# Temp.net
KiCad netlist of a schematic drawn in EAGLE
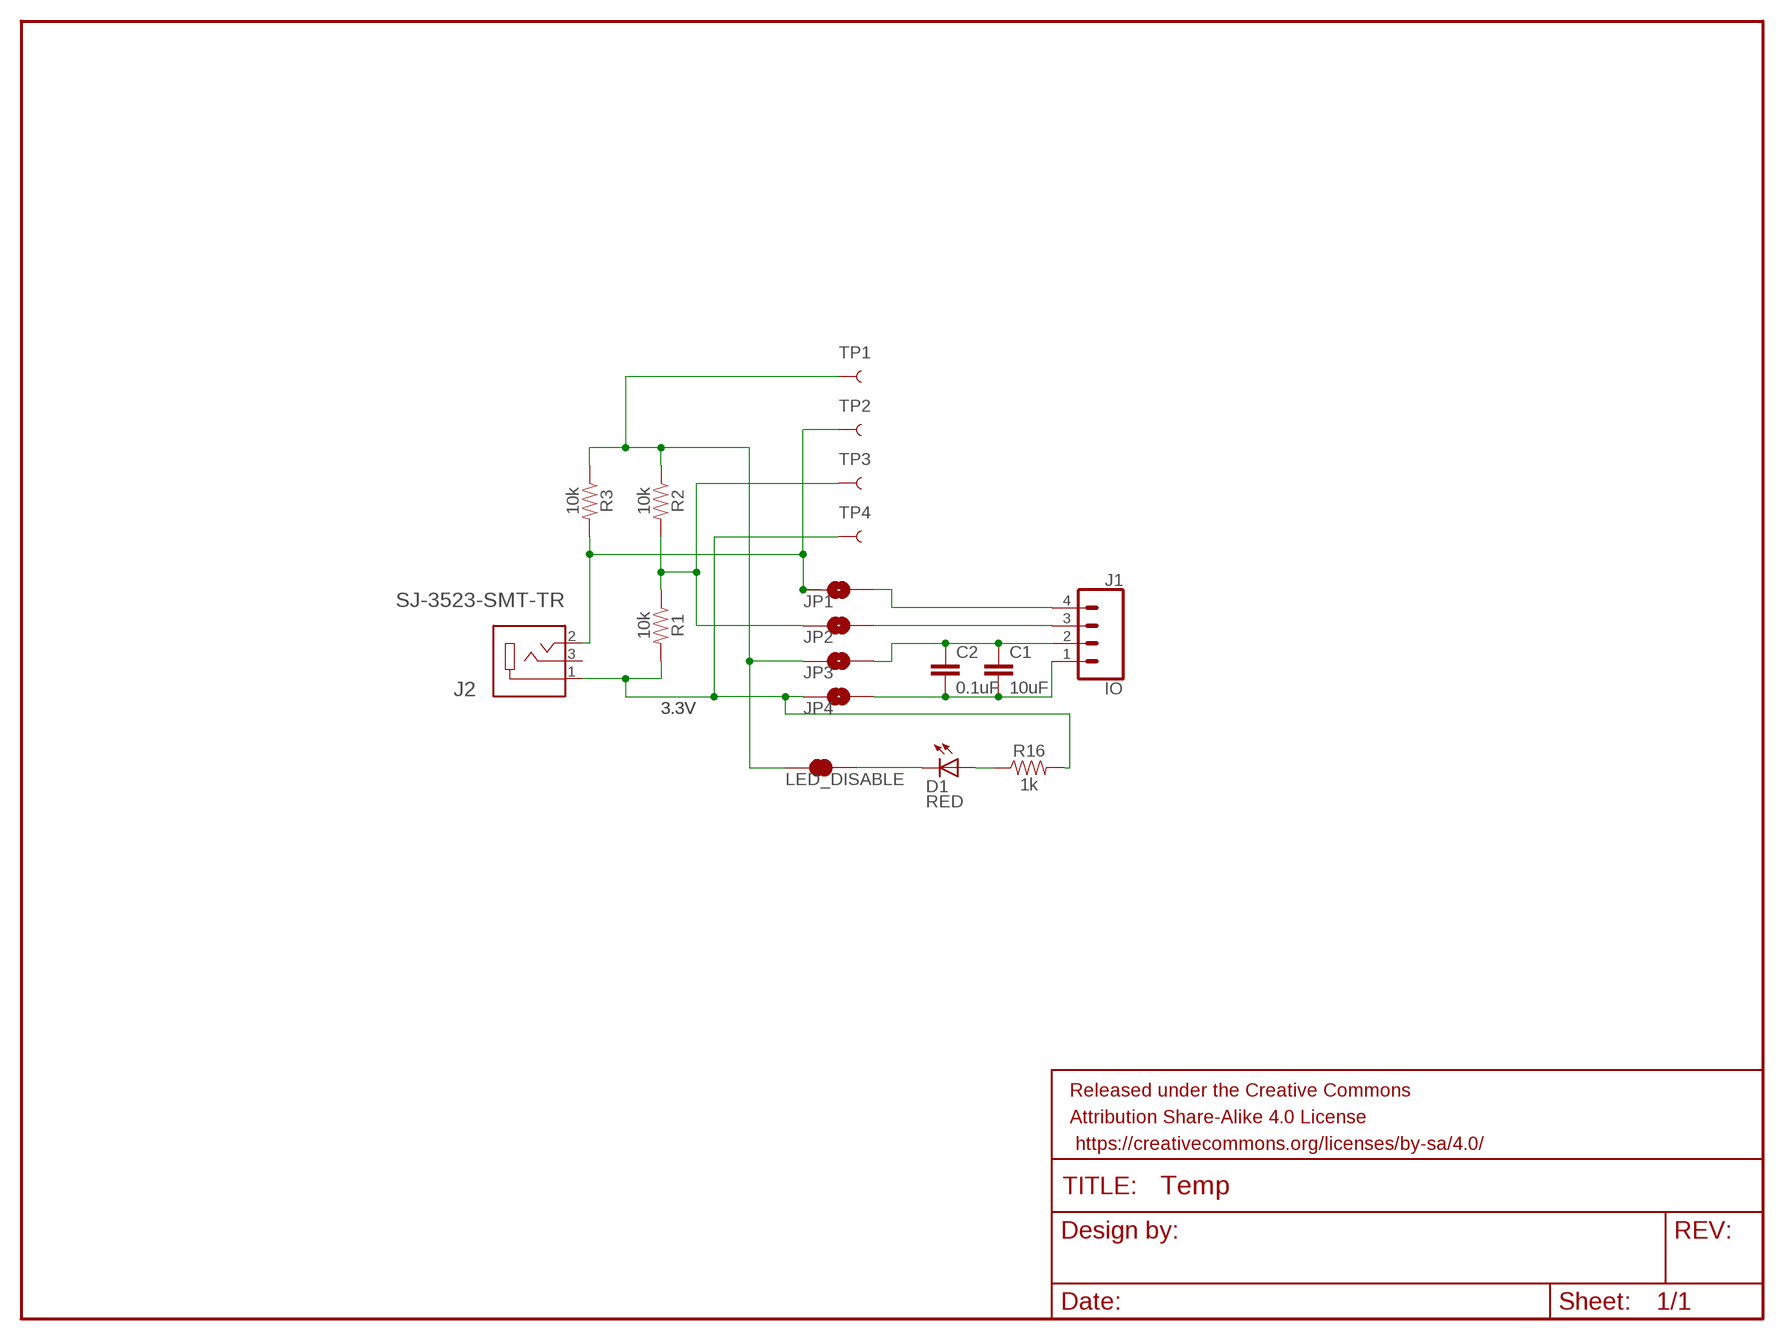
[diagram p0: schematic, sheet 1]

(export (version "E")
  (design (tool "Eeschema 10.0.6"))
  (components
    (comp (ref "C1")
      (value "10uF")
      (footprint "eagle-import:0603")
      (libsource (lib "eagle-import") (part "10UF-0603-6.3V-20%"))
    )
    (comp (ref "C2")
      (value "0.1uF")
      (footprint "eagle-import:0603")
      (libsource (lib "eagle-import") (part "0.1UF-0603-25V-(+80/-20%)"))
    )
    (comp (ref "D1")
      (value "RED")
      (footprint "eagle-import:LED-0603")
      (libsource (lib "eagle-import") (part "LED-RED0603"))
    )
    (comp (ref "FRAME1")
      (value "FRAME-LETTERNO_PACKAGE")
      (footprint "eagle-import:DUMMY")
      (fields (field (name "DESIGNER") "Nobody"))
      (libsource (lib "eagle-import") (part "FRAME-LETTERNO_PACKAGE"))
    )
    (comp (ref "J1")
      (value "IO")
      (footprint "eagle-import:1X04")
      (libsource (lib "eagle-import") (part "CONN_04"))
    )
    (comp (ref "J2")
      (value "SJ-3523-SMT-TR")
      (footprint "eagle-import:CUI_SJ-3523-SMT-TR")
      (fields (field (name "MF") "CUI Devices"))
      (libsource (lib "eagle-import") (part "SJ-3523-SMT-TR"))
    )
    (comp (ref "JP1")
      (value "JUMPER-SMT_2_NO_NO-SILK")
      (footprint "eagle-import:SMT-JUMPER_2_NO_NO-SILK")
      (libsource (lib "eagle-import") (part "JUMPER-SMT_2_NO_NO-SILK"))
    )
    (comp (ref "JP2")
      (value "JUMPER-SMT_2_NO_NO-SILK")
      (footprint "eagle-import:SMT-JUMPER_2_NO_NO-SILK")
      (libsource (lib "eagle-import") (part "JUMPER-SMT_2_NO_NO-SILK"))
    )
    (comp (ref "JP3")
      (value "JUMPER-SMT_2_NO_NO-SILK")
      (footprint "eagle-import:SMT-JUMPER_2_NO_NO-SILK")
      (libsource (lib "eagle-import") (part "JUMPER-SMT_2_NO_NO-SILK"))
    )
    (comp (ref "JP4")
      (value "JUMPER-SMT_2_NO_NO-SILK")
      (footprint "eagle-import:SMT-JUMPER_2_NO_NO-SILK")
      (libsource (lib "eagle-import") (part "JUMPER-SMT_2_NO_NO-SILK"))
    )
    (comp (ref "LED_DISABLE")
      (value "JUMPER-SMT_2_NC_TRACE_SILK")
      (footprint "eagle-import:SMT-JUMPER_2_NC_TRACE_SILK")
      (libsource (lib "eagle-import") (part "JUMPER-SMT_2_NC_TRACE_SILK"))
    )
    (comp (ref "R1")
      (value "10k")
      (footprint "eagle-import:0603")
      (libsource (lib "eagle-import") (part "10KOHM-0603-1/10W-1%"))
    )
    (comp (ref "R2")
      (value "10k")
      (footprint "eagle-import:0603")
      (libsource (lib "eagle-import") (part "10KOHM-0603-1/10W-1%"))
    )
    (comp (ref "R3")
      (value "10k")
      (footprint "eagle-import:0603")
      (libsource (lib "eagle-import") (part "10KOHM-0603-1/10W-1%"))
    )
    (comp (ref "R16")
      (value "1k")
      (footprint "eagle-import:0603")
      (libsource (lib "eagle-import") (part "1KOHM-0603-1/10W-1%"))
    )
    (comp (ref "TP1")
      (value "TEST-POINT3X5")
      (footprint "eagle-import:PAD.03X.05")
      (libsource (lib "eagle-import") (part "TEST-POINT3X5"))
    )
    (comp (ref "TP2")
      (value "TEST-POINT3X5")
      (footprint "eagle-import:PAD.03X.05")
      (libsource (lib "eagle-import") (part "TEST-POINT3X5"))
    )
    (comp (ref "TP3")
      (value "TEST-POINT3X5")
      (footprint "eagle-import:PAD.03X.05")
      (libsource (lib "eagle-import") (part "TEST-POINT3X5"))
    )
    (comp (ref "TP4")
      (value "TEST-POINT3X5")
      (footprint "eagle-import:PAD.03X.05")
      (libsource (lib "eagle-import") (part "TEST-POINT3X5"))
    )
  )
  (nets
    (net (code "1") (name "/3.3V") (class "Default")
      (node (ref "J2") (pin "1") (pinfunction "1_1") (pintype "passive"))
      (node (ref "JP4") (pin "1") (pinfunction "1_1") (pintype "passive"))
      (node (ref "R1") (pin "2") (pinfunction "2_2") (pintype "passive"))
      (node (ref "R16") (pin "2") (pinfunction "2_2") (pintype "passive"))
      (node (ref "TP4") (pin "P$1") (pinfunction "1_P$1") (pintype "bidirectional"))
    )
    (net (code "2") (name "Net-(C1-Pad1)") (class "Default")
      (node (ref "C1") (pin "1") (pinfunction "1_1") (pintype "passive"))
      (node (ref "C2") (pin "1") (pinfunction "1_1") (pintype "passive"))
      (node (ref "J1") (pin "2") (pinfunction "2_2") (pintype "passive"))
      (node (ref "JP3") (pin "2") (pinfunction "2_2") (pintype "passive"))
    )
    (net (code "3") (name "Net-(C1-Pad2)") (class "Default")
      (node (ref "C1") (pin "2") (pinfunction "2_2") (pintype "passive"))
      (node (ref "C2") (pin "2") (pinfunction "2_2") (pintype "passive"))
      (node (ref "J1") (pin "1") (pinfunction "1_1") (pintype "passive"))
      (node (ref "JP4") (pin "2") (pinfunction "2_2") (pintype "passive"))
    )
    (net (code "4") (name "Net-(D1-PadA)") (class "Default")
      (node (ref "D1") (pin "A") (pinfunction "A_A") (pintype "passive"))
      (node (ref "R16") (pin "1") (pinfunction "1_1") (pintype "passive"))
    )
    (net (code "5") (name "Net-(D1-PadC)") (class "Default")
      (node (ref "D1") (pin "C") (pinfunction "C_C") (pintype "passive"))
      (node (ref "LED_DISABLE") (pin "2") (pinfunction "2_2") (pintype "passive"))
    )
    (net (code "6") (name "Net-(J1-Pad3)") (class "Default")
      (node (ref "J1") (pin "3") (pinfunction "3_3") (pintype "passive"))
      (node (ref "JP2") (pin "2") (pinfunction "2_2") (pintype "passive"))
    )
    (net (code "7") (name "Net-(J1-Pad4)") (class "Default")
      (node (ref "J1") (pin "4") (pinfunction "4_4") (pintype "passive"))
      (node (ref "JP1") (pin "2") (pinfunction "2_2") (pintype "passive"))
    )
    (net (code "8") (name "Net-(TP1-1)") (class "Default")
      (node (ref "JP3") (pin "1") (pinfunction "1_1") (pintype "passive"))
      (node (ref "LED_DISABLE") (pin "1") (pinfunction "1_1") (pintype "passive"))
      (node (ref "R2") (pin "1") (pinfunction "1_1") (pintype "passive"))
      (node (ref "R3") (pin "1") (pinfunction "1_1") (pintype "passive"))
      (node (ref "TP1") (pin "P$1") (pinfunction "1_P$1") (pintype "bidirectional"))
    )
    (net (code "9") (name "Net-(TP2-1)") (class "Default")
      (node (ref "J2") (pin "2") (pinfunction "2_2") (pintype "passive"))
      (node (ref "JP1") (pin "1") (pinfunction "1_1") (pintype "passive"))
      (node (ref "R3") (pin "2") (pinfunction "2_2") (pintype "passive"))
      (node (ref "TP2") (pin "P$1") (pinfunction "1_P$1") (pintype "bidirectional"))
    )
    (net (code "10") (name "Net-(TP3-1)") (class "Default")
      (node (ref "JP2") (pin "1") (pinfunction "1_1") (pintype "passive"))
      (node (ref "R1") (pin "1") (pinfunction "1_1") (pintype "passive"))
      (node (ref "R2") (pin "2") (pinfunction "2_2") (pintype "passive"))
      (node (ref "TP3") (pin "P$1") (pinfunction "1_P$1") (pintype "bidirectional"))
    )
    (net (code "11") (name "unconnected-(J2-Pad3)") (class "Default")
      (node (ref "J2") (pin "3") (pinfunction "3_3") (pintype "passive"))
    )
  )
)
